# Sheet2.net
KiCad netlist of a schematic drawn in Altium Designer
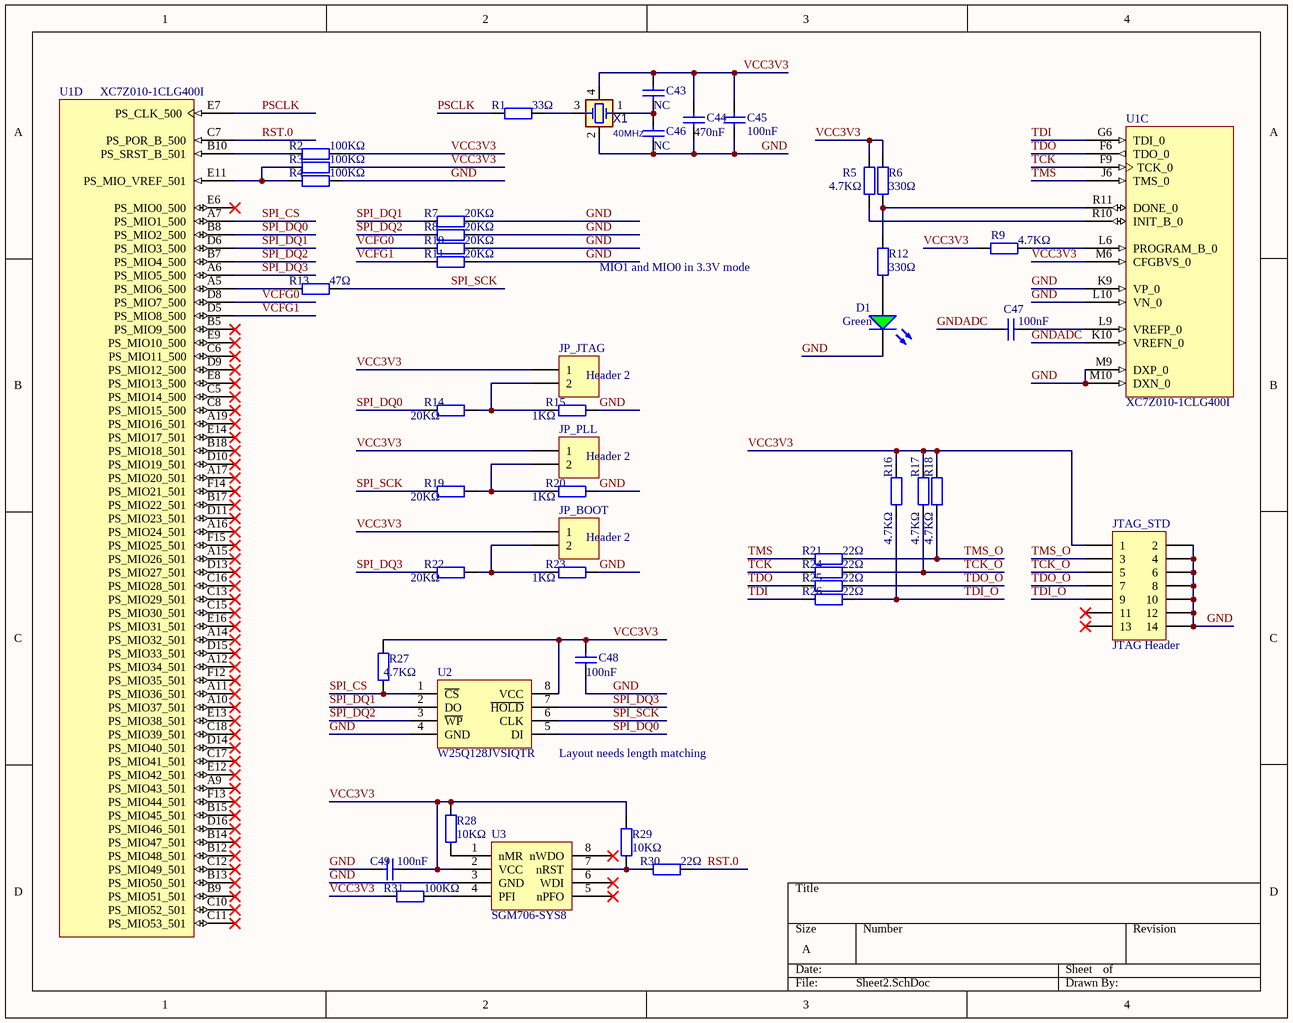
[diagram p0: Sheet2.SchDoc]

(export (version "E")
  (design (tool "Eeschema 10.0.6"))
  (components
    (comp (ref "C43")
      (value "NC")
      (footprint "0402_C")
      (description "贴片电容")
      (libsource (lib "Cap") (part "0402 470nF (474) 10% 10V"))
    )
    (comp (ref "C44")
      (value "470nF")
      (footprint "0402_C")
      (description "贴片电容")
      (libsource (lib "Cap") (part "0402 470nF (474) 10% 10V"))
    )
    (comp (ref "C45")
      (value "100nF")
      (footprint "1206_C")
      (description "贴片电容")
      (libsource (lib "Cap") (part "1206 100nF (104) 10% 50V"))
    )
    (comp (ref "C46")
      (value "NC")
      (footprint "0402_C")
      (description "贴片电容")
      (libsource (lib "Cap") (part "0402 470nF (474) 10% 10V"))
    )
    (comp (ref "C47")
      (value "100nF")
      (footprint "1206_C")
      (description "贴片电容")
      (libsource (lib "Cap") (part "1206 100nF (104) 10% 50V"))
    )
    (comp (ref "C48")
      (value "100nF")
      (footprint "1206_C")
      (description "贴片电容")
      (libsource (lib "Cap") (part "1206 100nF (104) 10% 50V"))
    )
    (comp (ref "C49")
      (value "100nF")
      (footprint "1206_C")
      (description "贴片电容")
      (libsource (lib "Cap") (part "1206 100nF (104) 10% 50V"))
    )
    (comp (ref "D1")
      (value "Green")
      (footprint "0805_LED_S1")
      (description "发光二极管")
      (libsource (lib "LED") (part "0805 翠绿"))
    )
    (comp (ref "JP_BOOT")
      (value "Header 2")
      (footprint "HDR1X2")
      (description "Header, 2-Pin")
      (fields (field (name "PUBLISHER") "Altium Limited"))
      (libsource (lib "Miscellaneous Connectors") (part "Header 2"))
    )
    (comp (ref "JP_JTAG")
      (value "Header 2")
      (footprint "HDR1X2")
      (description "Header, 2-Pin")
      (fields (field (name "PUBLISHER") "Altium Limited"))
      (libsource (lib "Miscellaneous Connectors") (part "Header 2"))
    )
    (comp (ref "JP_PLL")
      (value "Header 2")
      (footprint "HDR1X2")
      (description "Header, 2-Pin")
      (fields (field (name "PUBLISHER") "Altium Limited"))
      (libsource (lib "Miscellaneous Connectors") (part "Header 2"))
    )
    (comp (ref "JTAG_STD")
      (value "JTAG Header")
      (footprint "HDR2X7")
      (description "Header, 7-Pin, Dual row")
      (fields (field (name "PUBLISHER") "Altium Limited"))
      (libsource (lib "Miscellaneous Connectors") (part "Header 7X2"))
    )
    (comp (ref "R1")
      (value "33Ω")
      (footprint "0603_R")
      (description "贴片电阻")
      (libsource (lib "RES") (part "0603 33Ω (33R0) 1%"))
    )
    (comp (ref "R2")
      (value "100KΩ")
      (footprint "1206_R")
      (description "贴片电阻")
      (libsource (lib "RES") (part "1206 100KΩ (1003) 1%"))
    )
    (comp (ref "R3")
      (value "100KΩ")
      (footprint "1206_R")
      (description "贴片电阻")
      (libsource (lib "RES") (part "1206 100KΩ (1003) 1%"))
    )
    (comp (ref "R4")
      (value "100KΩ")
      (footprint "1206_R")
      (description "贴片电阻")
      (libsource (lib "RES") (part "1206 100KΩ (1003) 1%"))
    )
    (comp (ref "R5")
      (value "4.7KΩ")
      (footprint "1206_R")
      (description "贴片电阻")
      (libsource (lib "RES") (part "1206 4.7KΩ (4701) 1%"))
    )
    (comp (ref "R6")
      (value "330Ω")
      (footprint "0805_R")
      (description "贴片电阻")
      (libsource (lib "") (part "0805 330Ω (3300) 1%_1"))
    )
    (comp (ref "R7")
      (value "20KΩ")
      (footprint "0805_R")
      (description "贴片电阻")
      (libsource (lib "RES") (part "0805 20KΩ (2002) 1%"))
    )
    (comp (ref "R8")
      (value "20KΩ")
      (footprint "0805_R")
      (description "贴片电阻")
      (libsource (lib "RES") (part "0805 20KΩ (2002) 1%"))
    )
    (comp (ref "R9")
      (value "4.7KΩ")
      (footprint "1206_R")
      (description "贴片电阻")
      (libsource (lib "") (part "1206 4.7KΩ (4701) 1%_1"))
    )
    (comp (ref "R10")
      (value "20KΩ")
      (footprint "0805_R")
      (description "贴片电阻")
      (libsource (lib "RES") (part "0805 20KΩ (2002) 1%"))
    )
    (comp (ref "R11")
      (value "20KΩ")
      (footprint "0805_R")
      (description "贴片电阻")
      (libsource (lib "RES") (part "0805 20KΩ (2002) 1%"))
    )
    (comp (ref "R12")
      (value "330Ω")
      (footprint "0805_R")
      (description "贴片电阻")
      (libsource (lib "RES") (part "0805 330Ω (3300) 1%"))
    )
    (comp (ref "R13")
      (value "47Ω")
      (footprint "0805_R")
      (description "贴片电阻")
      (libsource (lib "RES") (part "0805 47Ω (47R0) 1%"))
    )
    (comp (ref "R14")
      (value "20KΩ")
      (footprint "0805_R")
      (description "贴片电阻")
      (libsource (lib "RES") (part "0805 20KΩ (2002) 1%"))
    )
    (comp (ref "R15")
      (value "1KΩ")
      (footprint "1206_R")
      (description "贴片电阻")
      (libsource (lib "RES") (part "1206 1KΩ (1001) 1%"))
    )
    (comp (ref "R16")
      (value "4.7KΩ")
      (footprint "1206_R")
      (description "贴片电阻")
      (libsource (lib "RES") (part "1206 4.7KΩ (4701) 1%"))
    )
    (comp (ref "R17")
      (value "4.7KΩ")
      (footprint "1206_R")
      (description "贴片电阻")
      (libsource (lib "RES") (part "1206 4.7KΩ (4701) 1%"))
    )
    (comp (ref "R18")
      (value "4.7KΩ")
      (footprint "1206_R")
      (description "贴片电阻")
      (libsource (lib "RES") (part "1206 4.7KΩ (4701) 1%"))
    )
    (comp (ref "R19")
      (value "20KΩ")
      (footprint "0805_R")
      (description "贴片电阻")
      (libsource (lib "RES") (part "0805 20KΩ (2002) 1%"))
    )
    (comp (ref "R20")
      (value "1KΩ")
      (footprint "1206_R")
      (description "贴片电阻")
      (libsource (lib "RES") (part "1206 1KΩ (1001) 1%"))
    )
    (comp (ref "R21")
      (value "22Ω")
      (footprint "1206_R")
      (description "贴片电阻")
      (libsource (lib "RES") (part "1206 22Ω (22R0) 1%"))
    )
    (comp (ref "R22")
      (value "20KΩ")
      (footprint "0805_R")
      (description "贴片电阻")
      (libsource (lib "RES") (part "0805 20KΩ (2002) 1%"))
    )
    (comp (ref "R23")
      (value "1KΩ")
      (footprint "1206_R")
      (description "贴片电阻")
      (libsource (lib "RES") (part "1206 1KΩ (1001) 1%"))
    )
    (comp (ref "R24")
      (value "22Ω")
      (footprint "1206_R")
      (description "贴片电阻")
      (libsource (lib "RES") (part "1206 22Ω (22R0) 1%"))
    )
    (comp (ref "R25")
      (value "22Ω")
      (footprint "1206_R")
      (description "贴片电阻")
      (libsource (lib "RES") (part "1206 22Ω (22R0) 1%"))
    )
    (comp (ref "R26")
      (value "22Ω")
      (footprint "1206_R")
      (description "贴片电阻")
      (libsource (lib "RES") (part "1206 22Ω (22R0) 1%"))
    )
    (comp (ref "R27")
      (value "4.7KΩ")
      (footprint "1206_R")
      (description "贴片电阻")
      (libsource (lib "RES") (part "1206 4.7KΩ (4701) 1%"))
    )
    (comp (ref "R28")
      (value "10KΩ")
      (footprint "1206_R")
      (description "贴片电阻")
      (libsource (lib "RES") (part "1206 10KΩ (1002) 1%"))
    )
    (comp (ref "R29")
      (value "10KΩ")
      (footprint "1206_R")
      (description "贴片电阻")
      (libsource (lib "RES") (part "1206 10KΩ (1002) 1%"))
    )
    (comp (ref "R30")
      (value "22Ω")
      (footprint "1206_R")
      (description "贴片电阻")
      (libsource (lib "RES") (part "1206 22Ω (22R0) 1%"))
    )
    (comp (ref "R31")
      (value "100KΩ")
      (footprint "1206_R")
      (description "贴片电阻")
      (libsource (lib "RES") (part "1206 100KΩ (1003) 1%"))
    )
    (comp (ref "U1")
      (value "XC7Z010-1CLG400I")
      (footprint "CLG400")
      (fields (field (name "GENERIC PART NUMBER") "XC7Z010") (field (name "MANUFACTURER") "Xilinx"))
      (libsource (lib "Xilinx Zynq-7000") (part "XC7Z010-1CLG400I"))
    )
    (comp (ref "U2")
      (value "W25Q128JVSIQTR")
      (footprint "SOIC-8_208mil")
      (description "Flash ROM")
      (libsource (lib "IC") (part "W25Q128JVSIQTR_[C97521]"))
    )
    (comp (ref "U3")
      (value "SGM706-SYS8")
      (footprint "SOIC-8_150mil")
      (description "MCU  Supervisor, 150mil SOP-8")
      (libsource (lib "IC") (part "EEPROM/AT24C256C-SSHL-T_[C6482]"))
    )
    (comp (ref "X1")
      (value "40MHz")
      (footprint "XTL_4_3225")
      (description "CRYSTAL 40.00 MHZ 4pF, 10PPM")
      (fields (field (name "MANF") "ABRACON") (field (name "MANF_P#") "ABM8W-40.0000MHZ-4-B1U-T3"))
      (libsource (lib "Crystal Oscillator") (part "XTL_4_40MHz_3225A"))
    )
  )
  (nets
    (net (code "1") (name "/GND") (class "Default")
      (node (ref "C44") (pin "2") (pinfunction "2_2") (pintype "passive"))
      (node (ref "C45") (pin "1") (pinfunction "1_1") (pintype "passive"))
      (node (ref "C46") (pin "2") (pinfunction "2_2") (pintype "passive"))
      (node (ref "C48") (pin "1") (pinfunction "1_1") (pintype "passive"))
      (node (ref "C49") (pin "1") (pinfunction "1_1") (pintype "passive"))
      (node (ref "D1") (pin "K") (pinfunction "K_K") (pintype "passive"))
      (node (ref "JTAG_STD") (pin "10") (pinfunction "10_10") (pintype "passive"))
      (node (ref "JTAG_STD") (pin "12") (pinfunction "12_12") (pintype "passive"))
      (node (ref "JTAG_STD") (pin "14") (pinfunction "14_14") (pintype "passive"))
      (node (ref "JTAG_STD") (pin "2") (pinfunction "2_2") (pintype "passive"))
      (node (ref "JTAG_STD") (pin "4") (pinfunction "4_4") (pintype "passive"))
      (node (ref "JTAG_STD") (pin "6") (pinfunction "6_6") (pintype "passive"))
      (node (ref "JTAG_STD") (pin "8") (pinfunction "8_8") (pintype "passive"))
      (node (ref "R10") (pin "2") (pinfunction "2_2") (pintype "passive"))
      (node (ref "R11") (pin "2") (pinfunction "2_2") (pintype "passive"))
      (node (ref "R15") (pin "2") (pinfunction "2_2") (pintype "passive"))
      (node (ref "R20") (pin "2") (pinfunction "2_2") (pintype "passive"))
      (node (ref "R23") (pin "2") (pinfunction "2_2") (pintype "passive"))
      (node (ref "R4") (pin "2") (pinfunction "2_2") (pintype "passive"))
      (node (ref "R7") (pin "2") (pinfunction "2_2") (pintype "passive"))
      (node (ref "R8") (pin "2") (pinfunction "2_2") (pintype "passive"))
      (node (ref "U1") (pin "K9") (pinfunction "VP_0_K9") (pintype "input"))
      (node (ref "U1") (pin "L10") (pinfunction "VN_0_L10") (pintype "input"))
      (node (ref "U1") (pin "M10") (pinfunction "DXN_0_M10") (pintype "input"))
      (node (ref "U1") (pin "M9") (pinfunction "DXP_0_M9") (pintype "input"))
      (node (ref "U2") (pin "4") (pinfunction "GND_4") (pintype "passive"))
      (node (ref "U3") (pin "3") (pinfunction "GND_3") (pintype "passive"))
      (node (ref "X1") (pin "2") (pinfunction "GND1_2") (pintype "passive"))
    )
    (net (code "2") (name "/GNDADC") (class "Default")
      (node (ref "C47") (pin "1") (pinfunction "1_1") (pintype "passive"))
      (node (ref "U1") (pin "K10") (pinfunction "VREFN_0_K10") (pintype "input"))
    )
    (net (code "3") (name "/PSCLK") (class "Default")
      (node (ref "R1") (pin "1") (pinfunction "1_1") (pintype "passive"))
      (node (ref "U1") (pin "E7") (pinfunction "PS_CLK_500_E7") (pintype "input"))
    )
    (net (code "4") (name "/RST.0") (class "Default")
      (node (ref "R30") (pin "2") (pinfunction "2_2") (pintype "passive"))
      (node (ref "U1") (pin "C7") (pinfunction "PS_POR_B_500_C7") (pintype "input"))
    )
    (net (code "5") (name "/SPI_CS") (class "Default")
      (node (ref "R27") (pin "1") (pinfunction "1_1") (pintype "passive"))
      (node (ref "U1") (pin "A7") (pinfunction "PS_MIO1_500_A7") (pintype "bidirectional"))
      (node (ref "U2") (pin "1") (pinfunction "~{CS}_1") (pintype "passive"))
    )
    (net (code "6") (name "/SPI_DQ0") (class "Default")
      (node (ref "R14") (pin "1") (pinfunction "1_1") (pintype "passive"))
      (node (ref "U1") (pin "B8") (pinfunction "PS_MIO2_500_B8") (pintype "bidirectional"))
      (node (ref "U2") (pin "5") (pinfunction "DI_5") (pintype "passive"))
    )
    (net (code "7") (name "/SPI_DQ1") (class "Default")
      (node (ref "R7") (pin "1") (pinfunction "1_1") (pintype "passive"))
      (node (ref "U1") (pin "D6") (pinfunction "PS_MIO3_500_D6") (pintype "bidirectional"))
      (node (ref "U2") (pin "2") (pinfunction "DO_2") (pintype "passive"))
    )
    (net (code "8") (name "/SPI_DQ2") (class "Default")
      (node (ref "R8") (pin "1") (pinfunction "1_1") (pintype "passive"))
      (node (ref "U1") (pin "B7") (pinfunction "PS_MIO4_500_B7") (pintype "bidirectional"))
      (node (ref "U2") (pin "3") (pinfunction "~{WP}_3") (pintype "passive"))
    )
    (net (code "9") (name "/SPI_DQ3") (class "Default")
      (node (ref "R22") (pin "1") (pinfunction "1_1") (pintype "passive"))
      (node (ref "U1") (pin "A6") (pinfunction "PS_MIO5_500_A6") (pintype "bidirectional"))
      (node (ref "U2") (pin "7") (pinfunction "~{HOLD}_7") (pintype "passive"))
    )
    (net (code "10") (name "/SPI_SCK") (class "Default")
      (node (ref "R13") (pin "2") (pinfunction "2_2") (pintype "passive"))
      (node (ref "R19") (pin "1") (pinfunction "1_1") (pintype "passive"))
      (node (ref "U2") (pin "6") (pinfunction "CLK_6") (pintype "passive"))
    )
    (net (code "11") (name "/TCK") (class "Default")
      (node (ref "R24") (pin "1") (pinfunction "1_1") (pintype "passive"))
      (node (ref "U1") (pin "F9") (pinfunction "TCK_0_F9") (pintype "input"))
    )
    (net (code "12") (name "/TCK_O") (class "Default")
      (node (ref "JTAG_STD") (pin "5") (pinfunction "5_5") (pintype "passive"))
      (node (ref "R17") (pin "1") (pinfunction "1_1") (pintype "passive"))
      (node (ref "R24") (pin "2") (pinfunction "2_2") (pintype "passive"))
    )
    (net (code "13") (name "/TDI") (class "Default")
      (node (ref "R26") (pin "1") (pinfunction "1_1") (pintype "passive"))
      (node (ref "U1") (pin "G6") (pinfunction "TDI_0_G6") (pintype "input"))
    )
    (net (code "14") (name "/TDI_O") (class "Default")
      (node (ref "JTAG_STD") (pin "9") (pinfunction "9_9") (pintype "passive"))
      (node (ref "R16") (pin "1") (pinfunction "1_1") (pintype "passive"))
      (node (ref "R26") (pin "2") (pinfunction "2_2") (pintype "passive"))
    )
    (net (code "15") (name "/TDO") (class "Default")
      (node (ref "R25") (pin "1") (pinfunction "1_1") (pintype "passive"))
      (node (ref "U1") (pin "F6") (pinfunction "TDO_0_F6") (pintype "output"))
    )
    (net (code "16") (name "/TDO_O") (class "Default")
      (node (ref "JTAG_STD") (pin "7") (pinfunction "7_7") (pintype "passive"))
      (node (ref "R25") (pin "2") (pinfunction "2_2") (pintype "passive"))
    )
    (net (code "17") (name "/TMS") (class "Default")
      (node (ref "R21") (pin "1") (pinfunction "1_1") (pintype "passive"))
      (node (ref "U1") (pin "J6") (pinfunction "TMS_0_J6") (pintype "input"))
    )
    (net (code "18") (name "/TMS_O") (class "Default")
      (node (ref "JTAG_STD") (pin "3") (pinfunction "3_3") (pintype "passive"))
      (node (ref "R18") (pin "1") (pinfunction "1_1") (pintype "passive"))
      (node (ref "R21") (pin "2") (pinfunction "2_2") (pintype "passive"))
    )
    (net (code "19") (name "/VCC3V3") (class "Default")
      (node (ref "C43") (pin "1") (pinfunction "1_1") (pintype "passive"))
      (node (ref "C44") (pin "1") (pinfunction "1_1") (pintype "passive"))
      (node (ref "C45") (pin "2") (pinfunction "2_2") (pintype "passive"))
      (node (ref "C48") (pin "2") (pinfunction "2_2") (pintype "passive"))
      (node (ref "C49") (pin "2") (pinfunction "2_2") (pintype "passive"))
      (node (ref "JP_BOOT") (pin "1") (pinfunction "1_1") (pintype "passive"))
      (node (ref "JP_JTAG") (pin "1") (pinfunction "1_1") (pintype "passive"))
      (node (ref "JP_PLL") (pin "1") (pinfunction "1_1") (pintype "passive"))
      (node (ref "JTAG_STD") (pin "1") (pinfunction "1_1") (pintype "passive"))
      (node (ref "R16") (pin "2") (pinfunction "2_2") (pintype "passive"))
      (node (ref "R17") (pin "2") (pinfunction "2_2") (pintype "passive"))
      (node (ref "R18") (pin "2") (pinfunction "2_2") (pintype "passive"))
      (node (ref "R2") (pin "2") (pinfunction "2_2") (pintype "passive"))
      (node (ref "R27") (pin "2") (pinfunction "2_2") (pintype "passive"))
      (node (ref "R28") (pin "2") (pinfunction "2_2") (pintype "passive"))
      (node (ref "R29") (pin "2") (pinfunction "2_2") (pintype "passive"))
      (node (ref "R3") (pin "2") (pinfunction "2_2") (pintype "passive"))
      (node (ref "R31") (pin "1") (pinfunction "1_1") (pintype "passive"))
      (node (ref "R5") (pin "2") (pinfunction "2_2") (pintype "passive"))
      (node (ref "R6") (pin "1") (pinfunction "1_1") (pintype "passive"))
      (node (ref "R9") (pin "1") (pinfunction "1_1") (pintype "passive"))
      (node (ref "U1") (pin "M6") (pinfunction "CFGBVS_0_M6") (pintype "input"))
      (node (ref "U2") (pin "8") (pinfunction "VCC_8") (pintype "passive"))
      (node (ref "U3") (pin "2") (pinfunction "VCC_2") (pintype "passive"))
      (node (ref "X1") (pin "4") (pinfunction "GND2_4") (pintype "passive"))
    )
    (net (code "20") (name "/VCFG0") (class "Default")
      (node (ref "R10") (pin "1") (pinfunction "1_1") (pintype "passive"))
      (node (ref "U1") (pin "D8") (pinfunction "PS_MIO7_500_D8") (pintype "bidirectional"))
    )
    (net (code "21") (name "/VCFG1") (class "Default")
      (node (ref "R11") (pin "1") (pinfunction "1_1") (pintype "passive"))
      (node (ref "U1") (pin "D5") (pinfunction "PS_MIO8_500_D5") (pintype "bidirectional"))
    )
    (net (code "22") (name "Net-(D1-PadA)") (class "Default")
      (node (ref "D1") (pin "A") (pinfunction "A_A") (pintype "passive"))
      (node (ref "R12") (pin "1") (pinfunction "1_1") (pintype "passive"))
    )
    (net (code "23") (name "Net-(JP_BOOT-Pad2)") (class "Default")
      (node (ref "JP_BOOT") (pin "2") (pinfunction "2_2") (pintype "passive"))
      (node (ref "R22") (pin "2") (pinfunction "2_2") (pintype "passive"))
      (node (ref "R23") (pin "1") (pinfunction "1_1") (pintype "passive"))
    )
    (net (code "24") (name "Net-(JP_JTAG-Pad2)") (class "Default")
      (node (ref "JP_JTAG") (pin "2") (pinfunction "2_2") (pintype "passive"))
      (node (ref "R14") (pin "2") (pinfunction "2_2") (pintype "passive"))
      (node (ref "R15") (pin "1") (pinfunction "1_1") (pintype "passive"))
    )
    (net (code "25") (name "Net-(JP_PLL-Pad2)") (class "Default")
      (node (ref "JP_PLL") (pin "2") (pinfunction "2_2") (pintype "passive"))
      (node (ref "R19") (pin "2") (pinfunction "2_2") (pintype "passive"))
      (node (ref "R20") (pin "1") (pinfunction "1_1") (pintype "passive"))
    )
    (net (code "26") (name "Net-(U1C-DONE_0)") (class "Default")
      (node (ref "R12") (pin "2") (pinfunction "2_2") (pintype "passive"))
      (node (ref "R6") (pin "2") (pinfunction "2_2") (pintype "passive"))
      (node (ref "U1") (pin "R11") (pinfunction "DONE_0_R11") (pintype "bidirectional"))
    )
    (net (code "27") (name "Net-(U1C-INIT_B_0)") (class "Default")
      (node (ref "R5") (pin "1") (pinfunction "1_1") (pintype "passive"))
      (node (ref "U1") (pin "R10") (pinfunction "INIT_B_0_R10") (pintype "bidirectional"))
    )
    (net (code "28") (name "Net-(U1C-PROGRAM_B_0)") (class "Default")
      (node (ref "R9") (pin "2") (pinfunction "2_2") (pintype "passive"))
      (node (ref "U1") (pin "L6") (pinfunction "PROGRAM_B_0_L6") (pintype "input"))
    )
    (net (code "29") (name "Net-(U1C-VREFP_0)") (class "Default")
      (node (ref "C47") (pin "2") (pinfunction "2_2") (pintype "passive"))
      (node (ref "U1") (pin "L9") (pinfunction "VREFP_0_L9") (pintype "input"))
    )
    (net (code "30") (name "Net-(U1D-PS_MIO6_500)") (class "Default")
      (node (ref "R13") (pin "1") (pinfunction "1_1") (pintype "passive"))
      (node (ref "U1") (pin "A5") (pinfunction "PS_MIO6_500_A5") (pintype "bidirectional"))
    )
    (net (code "31") (name "Net-(U1D-PS_MIO_VREF_501)") (class "Default")
      (node (ref "R3") (pin "1") (pinfunction "1_1") (pintype "passive"))
      (node (ref "R4") (pin "1") (pinfunction "1_1") (pintype "passive"))
      (node (ref "U1") (pin "E11") (pinfunction "PS_MIO_VREF_501_E11") (pintype "input"))
    )
    (net (code "32") (name "Net-(U1D-PS_SRST_B_501)") (class "Default")
      (node (ref "R2") (pin "1") (pinfunction "1_1") (pintype "passive"))
      (node (ref "U1") (pin "B10") (pinfunction "PS_SRST_B_501_B10") (pintype "input"))
    )
    (net (code "33") (name "Net-(U3-PFI)") (class "Default")
      (node (ref "R31") (pin "2") (pinfunction "2_2") (pintype "passive"))
      (node (ref "U3") (pin "4") (pinfunction "PFI_4") (pintype "passive"))
    )
    (net (code "34") (name "Net-(U3-nMR)") (class "Default")
      (node (ref "R28") (pin "1") (pinfunction "1_1") (pintype "passive"))
      (node (ref "U3") (pin "1") (pinfunction "nMR_1") (pintype "passive"))
    )
    (net (code "35") (name "Net-(U3-nRST)") (class "Default")
      (node (ref "R29") (pin "1") (pinfunction "1_1") (pintype "passive"))
      (node (ref "R30") (pin "1") (pinfunction "1_1") (pintype "passive"))
      (node (ref "U3") (pin "7") (pinfunction "nRST_7") (pintype "passive"))
    )
    (net (code "36") (name "Net-(X1-XA)") (class "Default")
      (node (ref "C43") (pin "2") (pinfunction "2_2") (pintype "passive"))
      (node (ref "C46") (pin "1") (pinfunction "1_1") (pintype "passive"))
      (node (ref "X1") (pin "1") (pinfunction "XA_1") (pintype "passive"))
    )
    (net (code "37") (name "Net-(X1-XB)") (class "Default")
      (node (ref "R1") (pin "2") (pinfunction "2_2") (pintype "passive"))
      (node (ref "X1") (pin "3") (pinfunction "XB_3") (pintype "passive"))
    )
    (net (code "38") (name "unconnected-(JTAG_STD-Pad11)") (class "Default")
      (node (ref "JTAG_STD") (pin "11") (pinfunction "11_11") (pintype "passive+no_connect"))
    )
    (net (code "39") (name "unconnected-(JTAG_STD-Pad13)") (class "Default")
      (node (ref "JTAG_STD") (pin "13") (pinfunction "13_13") (pintype "passive+no_connect"))
    )
    (net (code "40") (name "unconnected-(U1D-PS_MIO0_500-PadE6)") (class "Default")
      (node (ref "U1") (pin "E6") (pinfunction "PS_MIO0_500_E6") (pintype "bidirectional+no_connect"))
    )
    (net (code "41") (name "unconnected-(U1D-PS_MIO9_500-PadB5)") (class "Default")
      (node (ref "U1") (pin "B5") (pinfunction "PS_MIO9_500_B5") (pintype "bidirectional+no_connect"))
    )
    (net (code "42") (name "unconnected-(U1D-PS_MIO10_500-PadE9)") (class "Default")
      (node (ref "U1") (pin "E9") (pinfunction "PS_MIO10_500_E9") (pintype "bidirectional+no_connect"))
    )
    (net (code "43") (name "unconnected-(U1D-PS_MIO11_500-PadC6)") (class "Default")
      (node (ref "U1") (pin "C6") (pinfunction "PS_MIO11_500_C6") (pintype "bidirectional+no_connect"))
    )
    (net (code "44") (name "unconnected-(U1D-PS_MIO12_500-PadD9)") (class "Default")
      (node (ref "U1") (pin "D9") (pinfunction "PS_MIO12_500_D9") (pintype "bidirectional+no_connect"))
    )
    (net (code "45") (name "unconnected-(U1D-PS_MIO13_500-PadE8)") (class "Default")
      (node (ref "U1") (pin "E8") (pinfunction "PS_MIO13_500_E8") (pintype "bidirectional+no_connect"))
    )
    (net (code "46") (name "unconnected-(U1D-PS_MIO14_500-PadC5)") (class "Default")
      (node (ref "U1") (pin "C5") (pinfunction "PS_MIO14_500_C5") (pintype "bidirectional+no_connect"))
    )
    (net (code "47") (name "unconnected-(U1D-PS_MIO15_500-PadC8)") (class "Default")
      (node (ref "U1") (pin "C8") (pinfunction "PS_MIO15_500_C8") (pintype "bidirectional+no_connect"))
    )
    (net (code "48") (name "unconnected-(U1D-PS_MIO16_501-PadA19)") (class "Default")
      (node (ref "U1") (pin "A19") (pinfunction "PS_MIO16_501_A19") (pintype "bidirectional+no_connect"))
    )
    (net (code "49") (name "unconnected-(U1D-PS_MIO17_501-PadE14)") (class "Default")
      (node (ref "U1") (pin "E14") (pinfunction "PS_MIO17_501_E14") (pintype "bidirectional+no_connect"))
    )
    (net (code "50") (name "unconnected-(U1D-PS_MIO18_501-PadB18)") (class "Default")
      (node (ref "U1") (pin "B18") (pinfunction "PS_MIO18_501_B18") (pintype "bidirectional+no_connect"))
    )
    (net (code "51") (name "unconnected-(U1D-PS_MIO19_501-PadD10)") (class "Default")
      (node (ref "U1") (pin "D10") (pinfunction "PS_MIO19_501_D10") (pintype "bidirectional+no_connect"))
    )
    (net (code "52") (name "unconnected-(U1D-PS_MIO20_501-PadA17)") (class "Default")
      (node (ref "U1") (pin "A17") (pinfunction "PS_MIO20_501_A17") (pintype "bidirectional+no_connect"))
    )
    (net (code "53") (name "unconnected-(U1D-PS_MIO21_501-PadF14)") (class "Default")
      (node (ref "U1") (pin "F14") (pinfunction "PS_MIO21_501_F14") (pintype "bidirectional+no_connect"))
    )
    (net (code "54") (name "unconnected-(U1D-PS_MIO22_501-PadB17)") (class "Default")
      (node (ref "U1") (pin "B17") (pinfunction "PS_MIO22_501_B17") (pintype "bidirectional+no_connect"))
    )
    (net (code "55") (name "unconnected-(U1D-PS_MIO23_501-PadD11)") (class "Default")
      (node (ref "U1") (pin "D11") (pinfunction "PS_MIO23_501_D11") (pintype "bidirectional+no_connect"))
    )
    (net (code "56") (name "unconnected-(U1D-PS_MIO24_501-PadA16)") (class "Default")
      (node (ref "U1") (pin "A16") (pinfunction "PS_MIO24_501_A16") (pintype "bidirectional+no_connect"))
    )
    (net (code "57") (name "unconnected-(U1D-PS_MIO25_501-PadF15)") (class "Default")
      (node (ref "U1") (pin "F15") (pinfunction "PS_MIO25_501_F15") (pintype "bidirectional+no_connect"))
    )
    (net (code "58") (name "unconnected-(U1D-PS_MIO26_501-PadA15)") (class "Default")
      (node (ref "U1") (pin "A15") (pinfunction "PS_MIO26_501_A15") (pintype "bidirectional+no_connect"))
    )
    (net (code "59") (name "unconnected-(U1D-PS_MIO27_501-PadD13)") (class "Default")
      (node (ref "U1") (pin "D13") (pinfunction "PS_MIO27_501_D13") (pintype "bidirectional+no_connect"))
    )
    (net (code "60") (name "unconnected-(U1D-PS_MIO28_501-PadC16)") (class "Default")
      (node (ref "U1") (pin "C16") (pinfunction "PS_MIO28_501_C16") (pintype "bidirectional+no_connect"))
    )
    (net (code "61") (name "unconnected-(U1D-PS_MIO29_501-PadC13)") (class "Default")
      (node (ref "U1") (pin "C13") (pinfunction "PS_MIO29_501_C13") (pintype "bidirectional+no_connect"))
    )
    (net (code "62") (name "unconnected-(U1D-PS_MIO30_501-PadC15)") (class "Default")
      (node (ref "U1") (pin "C15") (pinfunction "PS_MIO30_501_C15") (pintype "bidirectional+no_connect"))
    )
    (net (code "63") (name "unconnected-(U1D-PS_MIO31_501-PadE16)") (class "Default")
      (node (ref "U1") (pin "E16") (pinfunction "PS_MIO31_501_E16") (pintype "bidirectional+no_connect"))
    )
    (net (code "64") (name "unconnected-(U1D-PS_MIO32_501-PadA14)") (class "Default")
      (node (ref "U1") (pin "A14") (pinfunction "PS_MIO32_501_A14") (pintype "bidirectional+no_connect"))
    )
    (net (code "65") (name "unconnected-(U1D-PS_MIO33_501-PadD15)") (class "Default")
      (node (ref "U1") (pin "D15") (pinfunction "PS_MIO33_501_D15") (pintype "bidirectional+no_connect"))
    )
    (net (code "66") (name "unconnected-(U1D-PS_MIO34_501-PadA12)") (class "Default")
      (node (ref "U1") (pin "A12") (pinfunction "PS_MIO34_501_A12") (pintype "bidirectional+no_connect"))
    )
    (net (code "67") (name "unconnected-(U1D-PS_MIO35_501-PadF12)") (class "Default")
      (node (ref "U1") (pin "F12") (pinfunction "PS_MIO35_501_F12") (pintype "bidirectional+no_connect"))
    )
    (net (code "68") (name "unconnected-(U1D-PS_MIO36_501-PadA11)") (class "Default")
      (node (ref "U1") (pin "A11") (pinfunction "PS_MIO36_501_A11") (pintype "bidirectional+no_connect"))
    )
    (net (code "69") (name "unconnected-(U1D-PS_MIO37_501-PadA10)") (class "Default")
      (node (ref "U1") (pin "A10") (pinfunction "PS_MIO37_501_A10") (pintype "bidirectional+no_connect"))
    )
    (net (code "70") (name "unconnected-(U1D-PS_MIO38_501-PadE13)") (class "Default")
      (node (ref "U1") (pin "E13") (pinfunction "PS_MIO38_501_E13") (pintype "bidirectional+no_connect"))
    )
    (net (code "71") (name "unconnected-(U1D-PS_MIO39_501-PadC18)") (class "Default")
      (node (ref "U1") (pin "C18") (pinfunction "PS_MIO39_501_C18") (pintype "bidirectional+no_connect"))
    )
    (net (code "72") (name "unconnected-(U1D-PS_MIO40_501-PadD14)") (class "Default")
      (node (ref "U1") (pin "D14") (pinfunction "PS_MIO40_501_D14") (pintype "bidirectional+no_connect"))
    )
    (net (code "73") (name "unconnected-(U1D-PS_MIO41_501-PadC17)") (class "Default")
      (node (ref "U1") (pin "C17") (pinfunction "PS_MIO41_501_C17") (pintype "bidirectional+no_connect"))
    )
    (net (code "74") (name "unconnected-(U1D-PS_MIO42_501-PadE12)") (class "Default")
      (node (ref "U1") (pin "E12") (pinfunction "PS_MIO42_501_E12") (pintype "bidirectional+no_connect"))
    )
    (net (code "75") (name "unconnected-(U1D-PS_MIO43_501-PadA9)") (class "Default")
      (node (ref "U1") (pin "A9") (pinfunction "PS_MIO43_501_A9") (pintype "bidirectional+no_connect"))
    )
    (net (code "76") (name "unconnected-(U1D-PS_MIO44_501-PadF13)") (class "Default")
      (node (ref "U1") (pin "F13") (pinfunction "PS_MIO44_501_F13") (pintype "bidirectional+no_connect"))
    )
    (net (code "77") (name "unconnected-(U1D-PS_MIO45_501-PadB15)") (class "Default")
      (node (ref "U1") (pin "B15") (pinfunction "PS_MIO45_501_B15") (pintype "bidirectional+no_connect"))
    )
    (net (code "78") (name "unconnected-(U1D-PS_MIO46_501-PadD16)") (class "Default")
      (node (ref "U1") (pin "D16") (pinfunction "PS_MIO46_501_D16") (pintype "bidirectional+no_connect"))
    )
    (net (code "79") (name "unconnected-(U1D-PS_MIO47_501-PadB14)") (class "Default")
      (node (ref "U1") (pin "B14") (pinfunction "PS_MIO47_501_B14") (pintype "bidirectional+no_connect"))
    )
    (net (code "80") (name "unconnected-(U1D-PS_MIO48_501-PadB12)") (class "Default")
      (node (ref "U1") (pin "B12") (pinfunction "PS_MIO48_501_B12") (pintype "bidirectional+no_connect"))
    )
    (net (code "81") (name "unconnected-(U1D-PS_MIO49_501-PadC12)") (class "Default")
      (node (ref "U1") (pin "C12") (pinfunction "PS_MIO49_501_C12") (pintype "bidirectional+no_connect"))
    )
    (net (code "82") (name "unconnected-(U1D-PS_MIO50_501-PadB13)") (class "Default")
      (node (ref "U1") (pin "B13") (pinfunction "PS_MIO50_501_B13") (pintype "bidirectional+no_connect"))
    )
    (net (code "83") (name "unconnected-(U1D-PS_MIO51_501-PadB9)") (class "Default")
      (node (ref "U1") (pin "B9") (pinfunction "PS_MIO51_501_B9") (pintype "bidirectional+no_connect"))
    )
    (net (code "84") (name "unconnected-(U1D-PS_MIO52_501-PadC10)") (class "Default")
      (node (ref "U1") (pin "C10") (pinfunction "PS_MIO52_501_C10") (pintype "bidirectional+no_connect"))
    )
    (net (code "85") (name "unconnected-(U1D-PS_MIO53_501-PadC11)") (class "Default")
      (node (ref "U1") (pin "C11") (pinfunction "PS_MIO53_501_C11") (pintype "bidirectional+no_connect"))
    )
    (net (code "86") (name "unconnected-(U3-WDI-Pad6)") (class "Default")
      (node (ref "U3") (pin "6") (pinfunction "WDI_6") (pintype "passive+no_connect"))
    )
    (net (code "87") (name "unconnected-(U3-nPFO-Pad5)") (class "Default")
      (node (ref "U3") (pin "5") (pinfunction "nPFO_5") (pintype "passive+no_connect"))
    )
    (net (code "88") (name "unconnected-(U3-nWDO-Pad8)") (class "Default")
      (node (ref "U3") (pin "8") (pinfunction "nWDO_8") (pintype "passive+no_connect"))
    )
  )
)
